# serialmonitor.net
KiCad netlist of a schematic drawn in EAGLE
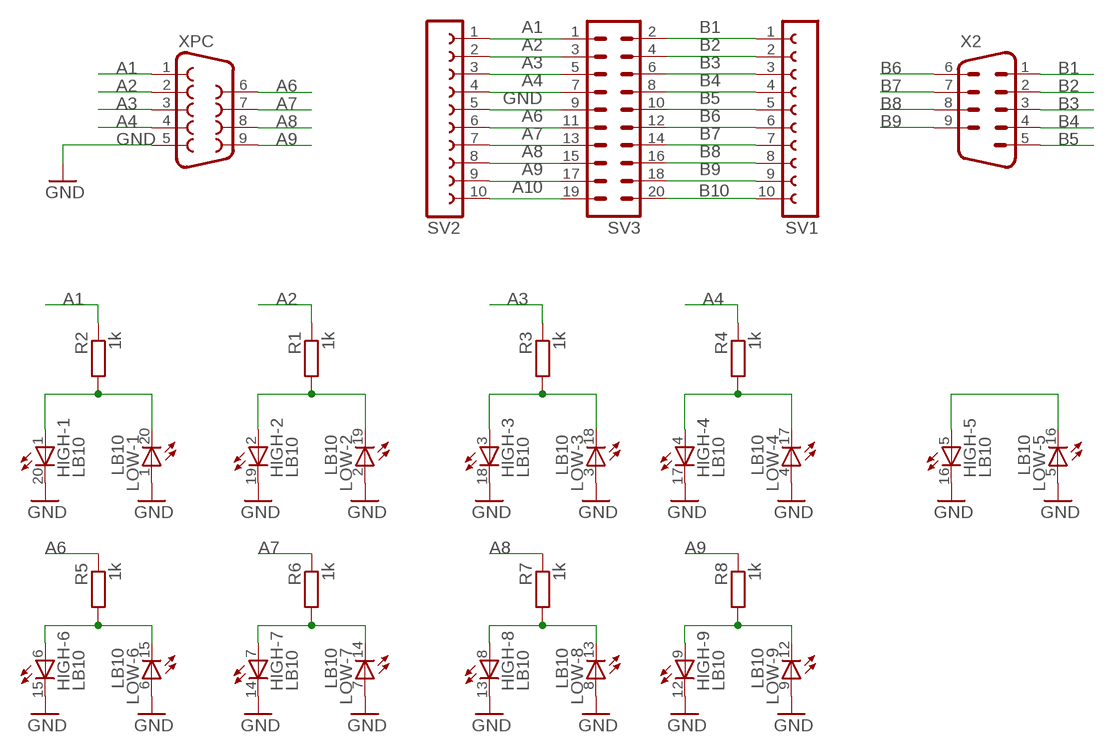
[diagram p0: schematic, sheet 1]

(export (version "E")
  (design (tool "Eeschema 10.0.6"))
  (components
    (comp (ref "HIGH")
      (value "LB10")
      (footprint "eagle-import:LB10")
      (libsource (lib "eagle-import") (part "LB10"))
    )
    (comp (ref "LOW")
      (value "LB10")
      (footprint "eagle-import:LB10")
      (libsource (lib "eagle-import") (part "LB10"))
    )
    (comp (ref "R1")
      (value "1k")
      (footprint "eagle-import:M0805")
      (libsource (lib "eagle-import") (part "R-EU_M0805"))
    )
    (comp (ref "R2")
      (value "1k")
      (footprint "eagle-import:M0805")
      (libsource (lib "eagle-import") (part "R-EU_M0805"))
    )
    (comp (ref "R3")
      (value "1k")
      (footprint "eagle-import:M0805")
      (libsource (lib "eagle-import") (part "R-EU_M0805"))
    )
    (comp (ref "R4")
      (value "1k")
      (footprint "eagle-import:M0805")
      (libsource (lib "eagle-import") (part "R-EU_M0805"))
    )
    (comp (ref "R5")
      (value "1k")
      (footprint "eagle-import:M0805")
      (libsource (lib "eagle-import") (part "R-EU_M0805"))
    )
    (comp (ref "R6")
      (value "1k")
      (footprint "eagle-import:M0805")
      (libsource (lib "eagle-import") (part "R-EU_M0805"))
    )
    (comp (ref "R7")
      (value "1k")
      (footprint "eagle-import:M0805")
      (libsource (lib "eagle-import") (part "R-EU_M0805"))
    )
    (comp (ref "R8")
      (value "1k")
      (footprint "eagle-import:M0805")
      (libsource (lib "eagle-import") (part "R-EU_M0805"))
    )
    (comp (ref "SV1")
      (value "FE10-1")
      (footprint "eagle-import:FE10")
      (libsource (lib "eagle-import") (part "FE10-1"))
    )
    (comp (ref "SV2")
      (value "FE10-1")
      (footprint "eagle-import:FE10")
      (libsource (lib "eagle-import") (part "FE10-1"))
    )
    (comp (ref "SV3")
      (value "MA10-2")
      (footprint "eagle-import:MA10-2")
      (libsource (lib "eagle-import") (part "MA10-2"))
    )
    (comp (ref "X2")
      (value "M09D")
      (footprint "eagle-import:M09D")
      (libsource (lib "eagle-import") (part "M09D"))
    )
    (comp (ref "XPC")
      (value "F09D")
      (footprint "eagle-import:F09D")
      (libsource (lib "eagle-import") (part "F09D"))
    )
  )
  (nets
    (net (code "1") (name "/A1") (class "Default")
      (node (ref "R2") (pin "1") (pinfunction "1_1") (pintype "passive"))
      (node (ref "SV2") (pin "1") (pinfunction "1_1") (pintype "passive"))
      (node (ref "SV3") (pin "1") (pinfunction "1_1") (pintype "passive"))
      (node (ref "XPC") (pin "1") (pinfunction "1_1") (pintype "passive"))
    )
    (net (code "2") (name "/A2") (class "Default")
      (node (ref "R1") (pin "1") (pinfunction "1_1") (pintype "passive"))
      (node (ref "SV2") (pin "2") (pinfunction "2_2") (pintype "passive"))
      (node (ref "SV3") (pin "3") (pinfunction "3_3") (pintype "passive"))
      (node (ref "XPC") (pin "2") (pinfunction "2_2") (pintype "passive"))
    )
    (net (code "3") (name "/A3") (class "Default")
      (node (ref "R3") (pin "1") (pinfunction "1_1") (pintype "passive"))
      (node (ref "SV2") (pin "3") (pinfunction "3_3") (pintype "passive"))
      (node (ref "SV3") (pin "5") (pinfunction "5_5") (pintype "passive"))
      (node (ref "XPC") (pin "3") (pinfunction "3_3") (pintype "passive"))
    )
    (net (code "4") (name "/A4") (class "Default")
      (node (ref "R4") (pin "1") (pinfunction "1_1") (pintype "passive"))
      (node (ref "SV2") (pin "4") (pinfunction "4_4") (pintype "passive"))
      (node (ref "SV3") (pin "7") (pinfunction "7_7") (pintype "passive"))
      (node (ref "XPC") (pin "4") (pinfunction "4_4") (pintype "passive"))
    )
    (net (code "5") (name "/A6") (class "Default")
      (node (ref "R5") (pin "1") (pinfunction "1_1") (pintype "passive"))
      (node (ref "SV2") (pin "6") (pinfunction "6_6") (pintype "passive"))
      (node (ref "SV3") (pin "11") (pinfunction "11_11") (pintype "passive"))
      (node (ref "XPC") (pin "6") (pinfunction "6_6") (pintype "passive"))
    )
    (net (code "6") (name "/A7") (class "Default")
      (node (ref "R6") (pin "1") (pinfunction "1_1") (pintype "passive"))
      (node (ref "SV2") (pin "7") (pinfunction "7_7") (pintype "passive"))
      (node (ref "SV3") (pin "13") (pinfunction "13_13") (pintype "passive"))
      (node (ref "XPC") (pin "7") (pinfunction "7_7") (pintype "passive"))
    )
    (net (code "7") (name "/A8") (class "Default")
      (node (ref "R7") (pin "1") (pinfunction "1_1") (pintype "passive"))
      (node (ref "SV2") (pin "8") (pinfunction "8_8") (pintype "passive"))
      (node (ref "SV3") (pin "15") (pinfunction "15_15") (pintype "passive"))
      (node (ref "XPC") (pin "8") (pinfunction "8_8") (pintype "passive"))
    )
    (net (code "8") (name "/A9") (class "Default")
      (node (ref "R8") (pin "1") (pinfunction "1_1") (pintype "passive"))
      (node (ref "SV2") (pin "9") (pinfunction "9_9") (pintype "passive"))
      (node (ref "SV3") (pin "17") (pinfunction "17_17") (pintype "passive"))
      (node (ref "XPC") (pin "9") (pinfunction "9_9") (pintype "passive"))
    )
    (net (code "9") (name "/A10") (class "Default")
      (node (ref "SV2") (pin "10") (pinfunction "10_10") (pintype "passive"))
      (node (ref "SV3") (pin "19") (pinfunction "19_19") (pintype "passive"))
    )
    (net (code "10") (name "/B1") (class "Default")
      (node (ref "SV1") (pin "1") (pinfunction "1_1") (pintype "passive"))
      (node (ref "SV3") (pin "2") (pinfunction "2_2") (pintype "passive"))
      (node (ref "X2") (pin "1") (pinfunction "1_1") (pintype "passive"))
    )
    (net (code "11") (name "/B2") (class "Default")
      (node (ref "SV1") (pin "2") (pinfunction "2_2") (pintype "passive"))
      (node (ref "SV3") (pin "4") (pinfunction "4_4") (pintype "passive"))
      (node (ref "X2") (pin "2") (pinfunction "2_2") (pintype "passive"))
    )
    (net (code "12") (name "/B3") (class "Default")
      (node (ref "SV1") (pin "3") (pinfunction "3_3") (pintype "passive"))
      (node (ref "SV3") (pin "6") (pinfunction "6_6") (pintype "passive"))
      (node (ref "X2") (pin "3") (pinfunction "3_3") (pintype "passive"))
    )
    (net (code "13") (name "/B4") (class "Default")
      (node (ref "SV1") (pin "4") (pinfunction "4_4") (pintype "passive"))
      (node (ref "SV3") (pin "8") (pinfunction "8_8") (pintype "passive"))
      (node (ref "X2") (pin "4") (pinfunction "4_4") (pintype "passive"))
    )
    (net (code "14") (name "/B5") (class "Default")
      (node (ref "SV1") (pin "5") (pinfunction "5_5") (pintype "passive"))
      (node (ref "SV3") (pin "10") (pinfunction "10_10") (pintype "passive"))
      (node (ref "X2") (pin "5") (pinfunction "5_5") (pintype "passive"))
    )
    (net (code "15") (name "/B6") (class "Default")
      (node (ref "SV1") (pin "6") (pinfunction "6_6") (pintype "passive"))
      (node (ref "SV3") (pin "12") (pinfunction "12_12") (pintype "passive"))
      (node (ref "X2") (pin "6") (pinfunction "6_6") (pintype "passive"))
    )
    (net (code "16") (name "/B7") (class "Default")
      (node (ref "SV1") (pin "7") (pinfunction "7_7") (pintype "passive"))
      (node (ref "SV3") (pin "14") (pinfunction "14_14") (pintype "passive"))
      (node (ref "X2") (pin "7") (pinfunction "7_7") (pintype "passive"))
    )
    (net (code "17") (name "/B8") (class "Default")
      (node (ref "SV1") (pin "8") (pinfunction "8_8") (pintype "passive"))
      (node (ref "SV3") (pin "16") (pinfunction "16_16") (pintype "passive"))
      (node (ref "X2") (pin "8") (pinfunction "8_8") (pintype "passive"))
    )
    (net (code "18") (name "/B9") (class "Default")
      (node (ref "SV1") (pin "9") (pinfunction "9_9") (pintype "passive"))
      (node (ref "SV3") (pin "18") (pinfunction "18_18") (pintype "passive"))
      (node (ref "X2") (pin "9") (pinfunction "9_9") (pintype "passive"))
    )
    (net (code "19") (name "/B10") (class "Default")
      (node (ref "SV1") (pin "10") (pinfunction "10_10") (pintype "passive"))
      (node (ref "SV3") (pin "20") (pinfunction "20_20") (pintype "passive"))
    )
    (net (code "20") (name "GND") (class "Default")
      (node (ref "HIGH") (pin "12") (pinfunction "C_12") (pintype "passive"))
      (node (ref "HIGH") (pin "13") (pinfunction "C_13") (pintype "passive"))
      (node (ref "HIGH") (pin "14") (pinfunction "C_14") (pintype "passive"))
      (node (ref "HIGH") (pin "15") (pinfunction "C_15") (pintype "passive"))
      (node (ref "HIGH") (pin "16") (pinfunction "C_16") (pintype "passive"))
      (node (ref "HIGH") (pin "17") (pinfunction "C_17") (pintype "passive"))
      (node (ref "HIGH") (pin "18") (pinfunction "C_18") (pintype "passive"))
      (node (ref "HIGH") (pin "19") (pinfunction "C_19") (pintype "passive"))
      (node (ref "HIGH") (pin "20") (pinfunction "C_20") (pintype "passive"))
      (node (ref "LOW") (pin "1") (pinfunction "A_1") (pintype "passive"))
      (node (ref "LOW") (pin "2") (pinfunction "A_2") (pintype "passive"))
      (node (ref "LOW") (pin "3") (pinfunction "A_3") (pintype "passive"))
      (node (ref "LOW") (pin "4") (pinfunction "A_4") (pintype "passive"))
      (node (ref "LOW") (pin "5") (pinfunction "A_5") (pintype "passive"))
      (node (ref "LOW") (pin "6") (pinfunction "A_6") (pintype "passive"))
      (node (ref "LOW") (pin "7") (pinfunction "A_7") (pintype "passive"))
      (node (ref "LOW") (pin "8") (pinfunction "A_8") (pintype "passive"))
      (node (ref "LOW") (pin "9") (pinfunction "A_9") (pintype "passive"))
      (node (ref "SV2") (pin "5") (pinfunction "5_5") (pintype "passive"))
      (node (ref "SV3") (pin "9") (pinfunction "9_9") (pintype "passive"))
      (node (ref "XPC") (pin "5") (pinfunction "5_5") (pintype "passive"))
    )
    (net (code "21") (name "Net-(HIGHA-A)") (class "Default")
      (node (ref "HIGH") (pin "1") (pinfunction "A_1") (pintype "passive"))
      (node (ref "LOW") (pin "20") (pinfunction "C_20") (pintype "passive"))
      (node (ref "R2") (pin "2") (pinfunction "2_2") (pintype "passive"))
    )
    (net (code "22") (name "Net-(HIGHC-A)") (class "Default")
      (node (ref "HIGH") (pin "2") (pinfunction "A_2") (pintype "passive"))
      (node (ref "LOW") (pin "19") (pinfunction "C_19") (pintype "passive"))
      (node (ref "R1") (pin "2") (pinfunction "2_2") (pintype "passive"))
    )
    (net (code "23") (name "Net-(HIGHD-A)") (class "Default")
      (node (ref "HIGH") (pin "3") (pinfunction "A_3") (pintype "passive"))
      (node (ref "LOW") (pin "18") (pinfunction "C_18") (pintype "passive"))
      (node (ref "R3") (pin "2") (pinfunction "2_2") (pintype "passive"))
    )
    (net (code "24") (name "Net-(HIGHE-A)") (class "Default")
      (node (ref "HIGH") (pin "4") (pinfunction "A_4") (pintype "passive"))
      (node (ref "LOW") (pin "17") (pinfunction "C_17") (pintype "passive"))
      (node (ref "R4") (pin "2") (pinfunction "2_2") (pintype "passive"))
    )
    (net (code "25") (name "Net-(HIGHF-A)") (class "Default")
      (node (ref "HIGH") (pin "5") (pinfunction "A_5") (pintype "passive"))
      (node (ref "LOW") (pin "16") (pinfunction "C_16") (pintype "passive"))
    )
    (net (code "26") (name "Net-(HIGHG-A)") (class "Default")
      (node (ref "HIGH") (pin "6") (pinfunction "A_6") (pintype "passive"))
      (node (ref "LOW") (pin "15") (pinfunction "C_15") (pintype "passive"))
      (node (ref "R5") (pin "2") (pinfunction "2_2") (pintype "passive"))
    )
    (net (code "27") (name "Net-(HIGHH-A)") (class "Default")
      (node (ref "HIGH") (pin "7") (pinfunction "A_7") (pintype "passive"))
      (node (ref "LOW") (pin "14") (pinfunction "C_14") (pintype "passive"))
      (node (ref "R6") (pin "2") (pinfunction "2_2") (pintype "passive"))
    )
    (net (code "28") (name "Net-(HIGHI-A)") (class "Default")
      (node (ref "HIGH") (pin "8") (pinfunction "A_8") (pintype "passive"))
      (node (ref "LOW") (pin "13") (pinfunction "C_13") (pintype "passive"))
      (node (ref "R7") (pin "2") (pinfunction "2_2") (pintype "passive"))
    )
    (net (code "29") (name "Net-(HIGHJ-A)") (class "Default")
      (node (ref "HIGH") (pin "9") (pinfunction "A_9") (pintype "passive"))
      (node (ref "LOW") (pin "12") (pinfunction "C_12") (pintype "passive"))
      (node (ref "R8") (pin "2") (pinfunction "2_2") (pintype "passive"))
    )
  )
)
